# WindPower_HAT_E.net
KiCad netlist of a schematic drawn in EAGLE
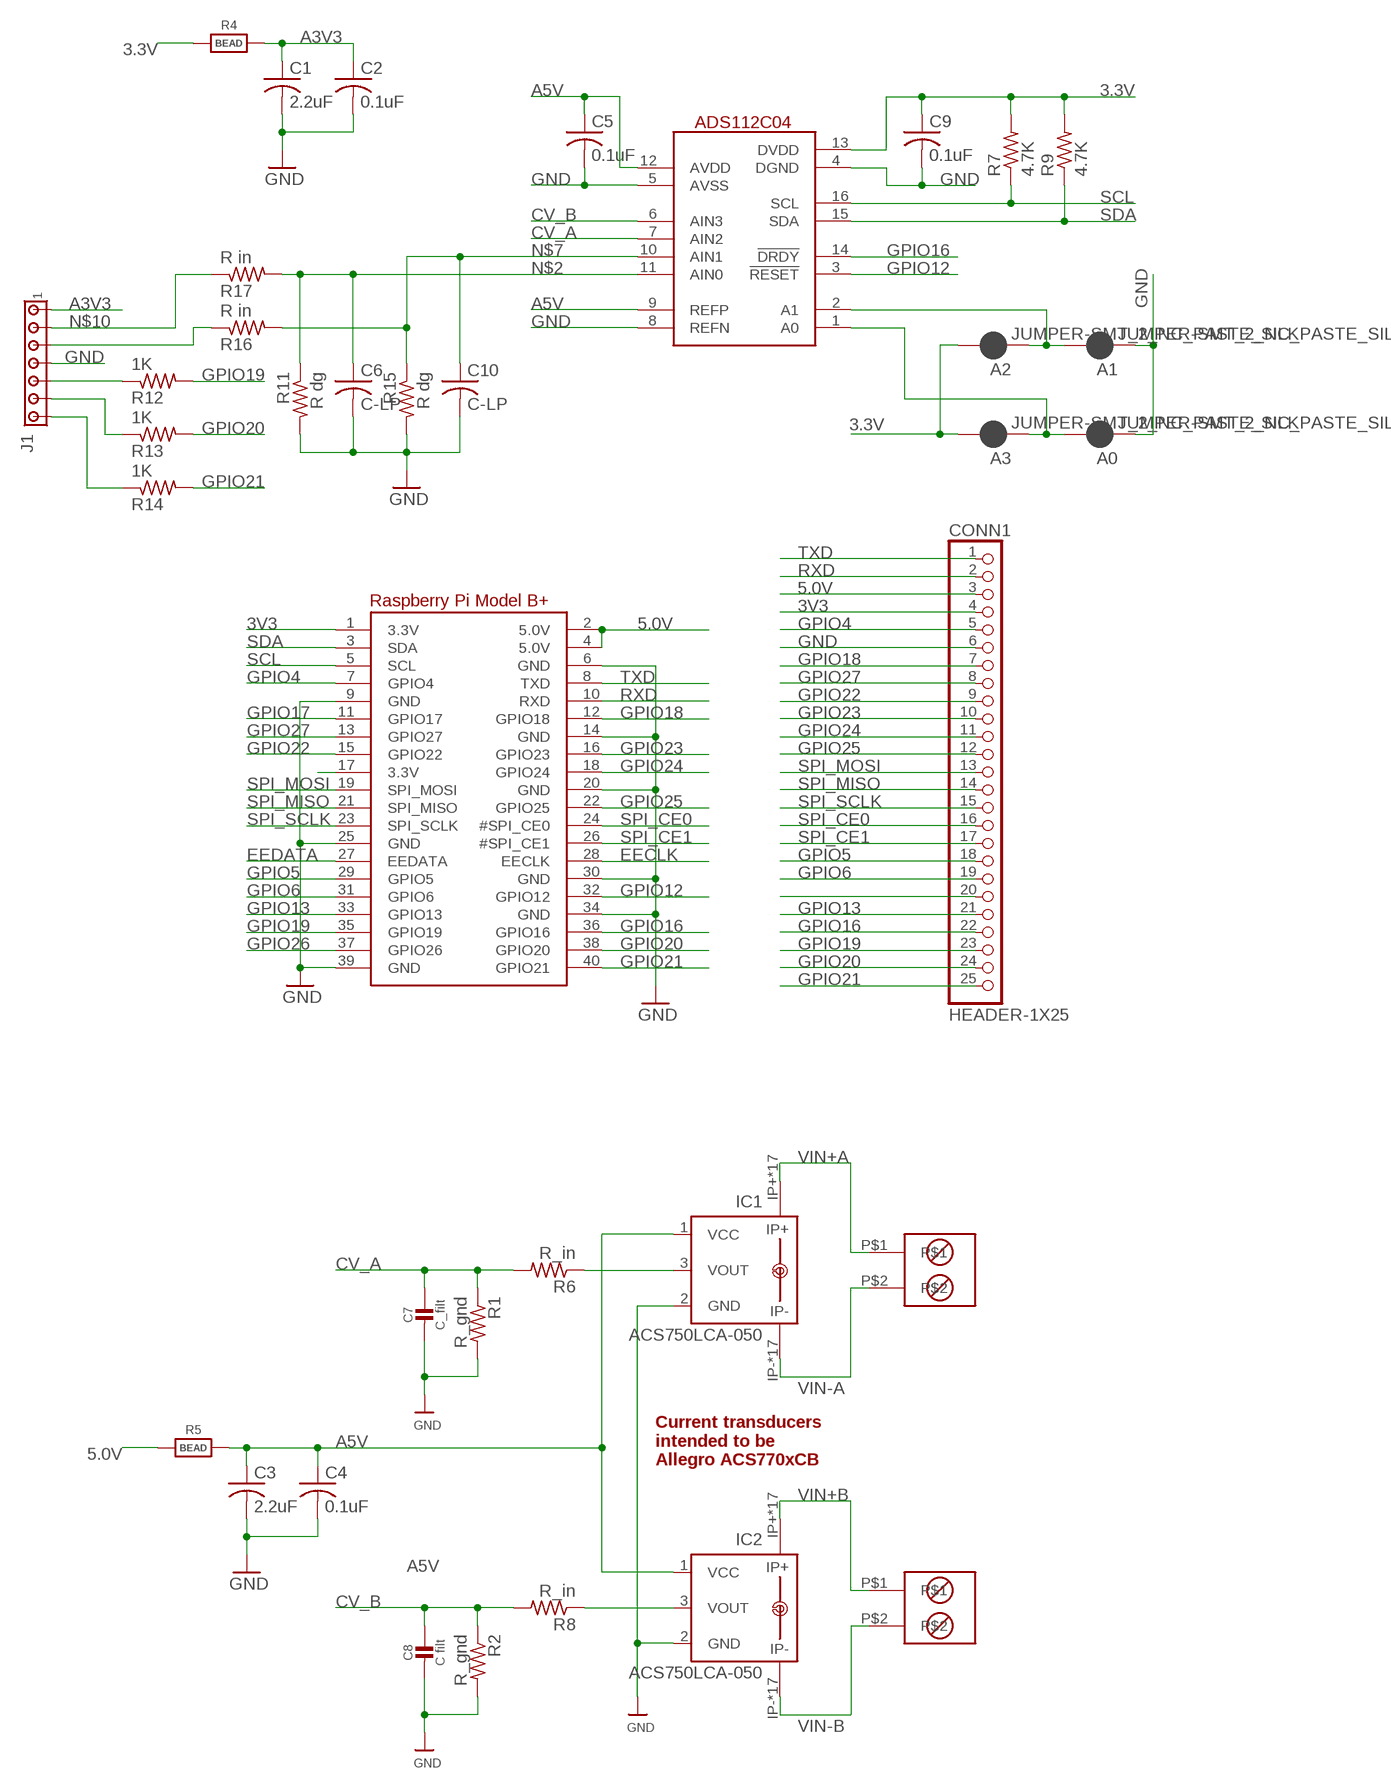
[diagram p0: schematic, sheet 1]

(export (version "E")
  (design (tool "Eeschema 10.0.6"))
  (components
    (comp (ref "A0")
      (value "JUMPER-SMT_2_NC_PASTE_SILK")
      (footprint "eagle-import:SMT-JUMPER_2_NC_PASTE_SILK")
      (libsource (lib "eagle-import") (part "JUMPER-SMT_2_NC_PASTE_SILK"))
    )
    (comp (ref "A1")
      (value "JUMPER-SMT_2_NC_PASTE_SILK")
      (footprint "eagle-import:SMT-JUMPER_2_NC_PASTE_SILK")
      (libsource (lib "eagle-import") (part "JUMPER-SMT_2_NC_PASTE_SILK"))
    )
    (comp (ref "A2")
      (value "JUMPER-SMT_2_NC_PASTE_SILK")
      (footprint "eagle-import:SMT-JUMPER_2_NC_PASTE_SILK")
      (libsource (lib "eagle-import") (part "JUMPER-SMT_2_NC_PASTE_SILK"))
    )
    (comp (ref "A3")
      (value "JUMPER-SMT_2_NC_PASTE_SILK")
      (footprint "eagle-import:SMT-JUMPER_2_NC_PASTE_SILK")
      (libsource (lib "eagle-import") (part "JUMPER-SMT_2_NC_PASTE_SILK"))
    )
    (comp (ref "ADS112C04")
      (value "ADS112C04TSSOP_FOR_TI_ADC")
      (footprint "eagle-import:SOP65P640X120-16N")
      (libsource (lib "eagle-import") (part "ADS112C04TSSOP_FOR_TI_ADC"))
    )
    (comp (ref "C1")
      (value "2.2uF")
      (footprint "eagle-import:C0805")
      (libsource (lib "eagle-import") (part "C-USC0805"))
    )
    (comp (ref "C2")
      (value "0.1uF")
      (footprint "eagle-import:C0805")
      (libsource (lib "eagle-import") (part "C-USC0805"))
    )
    (comp (ref "C3")
      (value "2.2uF")
      (footprint "eagle-import:C0805")
      (libsource (lib "eagle-import") (part "C-USC0805"))
    )
    (comp (ref "C4")
      (value "0.1uF")
      (footprint "eagle-import:C0805")
      (libsource (lib "eagle-import") (part "C-USC0805"))
    )
    (comp (ref "C5")
      (value "0.1uF")
      (footprint "eagle-import:C0805")
      (libsource (lib "eagle-import") (part "C-USC0805"))
    )
    (comp (ref "C6")
      (value "C-LP")
      (footprint "eagle-import:C0805")
      (libsource (lib "eagle-import") (part "C-USC0805"))
    )
    (comp (ref "C7")
      (value "C_filt")
      (footprint "eagle-import:0805-NO@1")
      (libsource (lib "eagle-import") (part "CAP_CERAMIC0805-NOOUTLINE"))
    )
    (comp (ref "C8")
      (value "C filt")
      (footprint "eagle-import:0805-NO@1")
      (libsource (lib "eagle-import") (part "CAP_CERAMIC0805-NOOUTLINE"))
    )
    (comp (ref "C9")
      (value "0.1uF")
      (footprint "eagle-import:C0805")
      (libsource (lib "eagle-import") (part "C-USC0805"))
    )
    (comp (ref "C10")
      (value "C-LP")
      (footprint "eagle-import:C0805")
      (libsource (lib "eagle-import") (part "C-USC0805"))
    )
    (comp (ref "CONN1")
      (value "HEADER-1X25")
      (footprint "eagle-import:1X25_ROUND_70MIL")
      (libsource (lib "eagle-import") (part "HEADER-1X25"))
    )
    (comp (ref "IC1")
      (value "ACS750LCA-050")
      (footprint "eagle-import:ACS75050")
      (fields (field (name "MF") "ALLEGRO MICROSYSTEMS, INC."))
      (libsource (lib "eagle-import") (part "ACS750CA-050L"))
    )
    (comp (ref "IC2")
      (value "ACS750LCA-050")
      (footprint "eagle-import:ACS75050")
      (fields (field (name "MF") "ALLEGRO MICROSYSTEMS, INC."))
      (libsource (lib "eagle-import") (part "ACS750CA-050L"))
    )
    (comp (ref "J1")
      (value "MTA07-100")
      (footprint "eagle-import:10X07MTA")
      (libsource (lib "eagle-import") (part "MTA07-100"))
    )
    (comp (ref "R1")
      (value "R_gnd")
      (footprint "eagle-import:R0805")
      (libsource (lib "eagle-import") (part "R-US_R0805"))
    )
    (comp (ref "R2")
      (value "R_gnd")
      (footprint "eagle-import:R0805")
      (libsource (lib "eagle-import") (part "R-US_R0805"))
    )
    (comp (ref "R4")
      (value "BEAD")
      (footprint "eagle-import:0805-NO")
      (libsource (lib "eagle-import") (part "RESISTOR0805_NOOUTLINE"))
    )
    (comp (ref "R5")
      (value "BEAD")
      (footprint "eagle-import:0805-NO")
      (libsource (lib "eagle-import") (part "RESISTOR0805_NOOUTLINE"))
    )
    (comp (ref "R6")
      (value "R_in")
      (footprint "eagle-import:R0805")
      (libsource (lib "eagle-import") (part "R-US_R0805"))
    )
    (comp (ref "R7")
      (value "4.7K")
      (footprint "eagle-import:R0805")
      (libsource (lib "eagle-import") (part "R-US_R0805"))
    )
    (comp (ref "R8")
      (value "R_in")
      (footprint "eagle-import:R0805")
      (libsource (lib "eagle-import") (part "R-US_R0805"))
    )
    (comp (ref "R9")
      (value "4.7K")
      (footprint "eagle-import:R0805")
      (libsource (lib "eagle-import") (part "R-US_R0805"))
    )
    (comp (ref "R11")
      (value "R dg")
      (footprint "eagle-import:R0805")
      (libsource (lib "eagle-import") (part "R-US_R0805"))
    )
    (comp (ref "R12")
      (value "1K")
      (footprint "eagle-import:R0805")
      (libsource (lib "eagle-import") (part "R-US_R0805"))
    )
    (comp (ref "R13")
      (value "1K")
      (footprint "eagle-import:R0805")
      (libsource (lib "eagle-import") (part "R-US_R0805"))
    )
    (comp (ref "R14")
      (value "1K")
      (footprint "eagle-import:R0805")
      (libsource (lib "eagle-import") (part "R-US_R0805"))
    )
    (comp (ref "R15")
      (value "R dg")
      (footprint "eagle-import:R0805")
      (libsource (lib "eagle-import") (part "R-US_R0805"))
    )
    (comp (ref "R16")
      (value "R in")
      (footprint "eagle-import:R0805")
      (libsource (lib "eagle-import") (part "R-US_R0805"))
    )
    (comp (ref "R17")
      (value "R in")
      (footprint "eagle-import:R0805")
      (libsource (lib "eagle-import") (part "R-US_R0805"))
    )
    (comp (ref "RPI1")
      (value "RASPBERRYPI_BPLUS_HATNOSLOTS")
      (footprint "eagle-import:PI_HAT_NOSLOTS")
      (libsource (lib "eagle-import") (part "RASPBERRYPI_BPLUS_HATNOSLOTS"))
    )
    (comp (ref "U$4")
      (value "SCREW-2-6.35MM")
      (footprint "eagle-import:SCREWY-2-6.35MM")
      (libsource (lib "eagle-import") (part "SCREW-2-6.35MM"))
    )
    (comp (ref "U$5")
      (value "SCREW-2-6.35MM")
      (footprint "eagle-import:SCREWY-2-6.35MM")
      (libsource (lib "eagle-import") (part "SCREW-2-6.35MM"))
    )
  )
  (nets
    (net (code "1") (name "/3V3") (class "Default")
      (node (ref "CONN1") (pin "4") (pinfunction "4_4") (pintype "passive"))
      (node (ref "RPI1") (pin "1") (pinfunction "3.3V_1") (pintype "power_in"))
    )
    (net (code "2") (name "/A3V3") (class "Default")
      (node (ref "C1") (pin "1") (pinfunction "1_1") (pintype "passive"))
      (node (ref "C2") (pin "1") (pinfunction "1_1") (pintype "passive"))
      (node (ref "J1") (pin "1") (pinfunction "1_1") (pintype "passive"))
      (node (ref "R4") (pin "2") (pinfunction "2_2") (pintype "passive"))
    )
    (net (code "3") (name "/A5V") (class "Default")
      (node (ref "ADS112C04") (pin "12") (pinfunction "AVDD_12") (pintype "power_in"))
      (node (ref "ADS112C04") (pin "9") (pinfunction "REFP_9") (pintype "input"))
      (node (ref "C3") (pin "1") (pinfunction "1_1") (pintype "passive"))
      (node (ref "C4") (pin "1") (pinfunction "1_1") (pintype "passive"))
      (node (ref "C5") (pin "1") (pinfunction "1_1") (pintype "passive"))
      (node (ref "IC1") (pin "1") (pinfunction "VCC_1") (pintype "power_in"))
      (node (ref "IC2") (pin "1") (pinfunction "VCC_1") (pintype "power_in"))
      (node (ref "R5") (pin "2") (pinfunction "2_2") (pintype "passive"))
    )
    (net (code "4") (name "/CV_A") (class "Default")
      (node (ref "ADS112C04") (pin "7") (pinfunction "AIN2_7") (pintype "input"))
      (node (ref "C7") (pin "1") (pinfunction "1_1") (pintype "passive"))
      (node (ref "R1") (pin "1") (pinfunction "1_1") (pintype "passive"))
      (node (ref "R6") (pin "2") (pinfunction "2_2") (pintype "passive"))
    )
    (net (code "5") (name "/CV_B") (class "Default")
      (node (ref "ADS112C04") (pin "6") (pinfunction "AIN3_6") (pintype "input"))
      (node (ref "C8") (pin "1") (pinfunction "1_1") (pintype "passive"))
      (node (ref "R2") (pin "1") (pinfunction "1_1") (pintype "passive"))
      (node (ref "R8") (pin "2") (pinfunction "2_2") (pintype "passive"))
    )
    (net (code "6") (name "/EECLK") (class "Default")
      (node (ref "RPI1") (pin "28") (pinfunction "EECLK_28") (pintype "power_in"))
    )
    (net (code "7") (name "/EEDATA") (class "Default")
      (node (ref "RPI1") (pin "27") (pinfunction "EEDATA_27") (pintype "bidirectional"))
    )
    (net (code "8") (name "/GPIO4") (class "Default")
      (node (ref "CONN1") (pin "5") (pinfunction "5_5") (pintype "passive"))
      (node (ref "RPI1") (pin "7") (pinfunction "GPIO4_7") (pintype "bidirectional"))
    )
    (net (code "9") (name "/GPIO5") (class "Default")
      (node (ref "CONN1") (pin "18") (pinfunction "18_18") (pintype "passive"))
      (node (ref "RPI1") (pin "29") (pinfunction "GPIO5_29") (pintype "bidirectional"))
    )
    (net (code "10") (name "/GPIO6") (class "Default")
      (node (ref "CONN1") (pin "19") (pinfunction "19_19") (pintype "passive"))
      (node (ref "RPI1") (pin "31") (pinfunction "GPIO6_31") (pintype "power_in"))
    )
    (net (code "11") (name "/GPIO12") (class "Default")
      (node (ref "ADS112C04") (pin "3") (pinfunction "~{RESET}_3") (pintype "output"))
      (node (ref "RPI1") (pin "32") (pinfunction "GPIO12_32") (pintype "bidirectional"))
    )
    (net (code "12") (name "/GPIO13") (class "Default")
      (node (ref "CONN1") (pin "21") (pinfunction "21_21") (pintype "passive"))
      (node (ref "RPI1") (pin "33") (pinfunction "GPIO13_33") (pintype "bidirectional"))
    )
    (net (code "13") (name "/GPIO16") (class "Default")
      (node (ref "ADS112C04") (pin "14") (pinfunction "~{DRDY}_14") (pintype "output"))
      (node (ref "CONN1") (pin "22") (pinfunction "22_22") (pintype "passive"))
      (node (ref "RPI1") (pin "36") (pinfunction "GPIO16_36") (pintype "power_in"))
    )
    (net (code "14") (name "/GPIO17") (class "Default")
      (node (ref "RPI1") (pin "11") (pinfunction "GPIO17_11") (pintype "bidirectional"))
    )
    (net (code "15") (name "/GPIO18") (class "Default")
      (node (ref "CONN1") (pin "7") (pinfunction "7_7") (pintype "passive"))
      (node (ref "RPI1") (pin "12") (pinfunction "GPIO18_12") (pintype "bidirectional"))
    )
    (net (code "16") (name "/GPIO19") (class "Default")
      (node (ref "CONN1") (pin "23") (pinfunction "23_23") (pintype "passive"))
      (node (ref "R12") (pin "2") (pinfunction "2_2") (pintype "passive"))
      (node (ref "RPI1") (pin "35") (pinfunction "GPIO19_35") (pintype "bidirectional"))
    )
    (net (code "17") (name "/GPIO20") (class "Default")
      (node (ref "CONN1") (pin "24") (pinfunction "24_24") (pintype "passive"))
      (node (ref "R13") (pin "2") (pinfunction "2_2") (pintype "passive"))
      (node (ref "RPI1") (pin "38") (pinfunction "GPIO20_38") (pintype "bidirectional"))
    )
    (net (code "18") (name "/GPIO21") (class "Default")
      (node (ref "CONN1") (pin "25") (pinfunction "25_25") (pintype "passive"))
      (node (ref "R14") (pin "2") (pinfunction "2_2") (pintype "passive"))
      (node (ref "RPI1") (pin "40") (pinfunction "GPIO21_40") (pintype "bidirectional"))
    )
    (net (code "19") (name "/GPIO22") (class "Default")
      (node (ref "CONN1") (pin "9") (pinfunction "9_9") (pintype "passive"))
      (node (ref "RPI1") (pin "15") (pinfunction "GPIO22_15") (pintype "bidirectional"))
    )
    (net (code "20") (name "/GPIO23") (class "Default")
      (node (ref "CONN1") (pin "10") (pinfunction "10_10") (pintype "passive"))
      (node (ref "RPI1") (pin "16") (pinfunction "GPIO23_16") (pintype "bidirectional"))
    )
    (net (code "21") (name "/GPIO24") (class "Default")
      (node (ref "CONN1") (pin "11") (pinfunction "11_11") (pintype "passive"))
      (node (ref "RPI1") (pin "18") (pinfunction "GPIO24_18") (pintype "bidirectional"))
    )
    (net (code "22") (name "/GPIO25") (class "Default")
      (node (ref "CONN1") (pin "12") (pinfunction "12_12") (pintype "passive"))
      (node (ref "RPI1") (pin "22") (pinfunction "GPIO25_22") (pintype "bidirectional"))
    )
    (net (code "23") (name "/GPIO26") (class "Default")
      (node (ref "RPI1") (pin "37") (pinfunction "GPIO26_37") (pintype "bidirectional"))
    )
    (net (code "24") (name "/GPIO27") (class "Default")
      (node (ref "CONN1") (pin "8") (pinfunction "8_8") (pintype "passive"))
      (node (ref "RPI1") (pin "13") (pinfunction "GPIO27_13") (pintype "bidirectional"))
    )
    (net (code "25") (name "/N$2") (class "Default")
      (node (ref "ADS112C04") (pin "11") (pinfunction "AIN0_11") (pintype "input"))
      (node (ref "C6") (pin "1") (pinfunction "1_1") (pintype "passive"))
      (node (ref "R11") (pin "1") (pinfunction "1_1") (pintype "passive"))
      (node (ref "R17") (pin "2") (pinfunction "2_2") (pintype "passive"))
    )
    (net (code "26") (name "/N$7") (class "Default")
      (node (ref "ADS112C04") (pin "10") (pinfunction "AIN1_10") (pintype "input"))
      (node (ref "C10") (pin "1") (pinfunction "1_1") (pintype "passive"))
      (node (ref "R15") (pin "1") (pinfunction "1_1") (pintype "passive"))
      (node (ref "R16") (pin "2") (pinfunction "2_2") (pintype "passive"))
    )
    (net (code "27") (name "/N$10") (class "Default")
      (node (ref "J1") (pin "2") (pinfunction "2_2") (pintype "passive"))
      (node (ref "R17") (pin "1") (pinfunction "1_1") (pintype "passive"))
    )
    (net (code "28") (name "/RXD") (class "Default")
      (node (ref "CONN1") (pin "2") (pinfunction "2_2") (pintype "passive"))
      (node (ref "RPI1") (pin "10") (pinfunction "RXD_10") (pintype "bidirectional"))
    )
    (net (code "29") (name "/SCL") (class "Default")
      (node (ref "ADS112C04") (pin "16") (pinfunction "SCL_16") (pintype "input"))
      (node (ref "R7") (pin "1") (pinfunction "1_1") (pintype "passive"))
      (node (ref "RPI1") (pin "5") (pinfunction "SCL_5") (pintype "bidirectional"))
    )
    (net (code "30") (name "/SDA") (class "Default")
      (node (ref "ADS112C04") (pin "15") (pinfunction "SDA_15") (pintype "bidirectional"))
      (node (ref "R9") (pin "1") (pinfunction "1_1") (pintype "passive"))
      (node (ref "RPI1") (pin "3") (pinfunction "SDA_3") (pintype "bidirectional"))
    )
    (net (code "31") (name "/SPI_CE0") (class "Default")
      (node (ref "CONN1") (pin "16") (pinfunction "16_16") (pintype "passive"))
      (node (ref "RPI1") (pin "24") (pinfunction "#SPI_CE0_24") (pintype "bidirectional"))
    )
    (net (code "32") (name "/SPI_CE1") (class "Default")
      (node (ref "CONN1") (pin "17") (pinfunction "17_17") (pintype "passive"))
      (node (ref "RPI1") (pin "26") (pinfunction "#SPI_CE1_26") (pintype "bidirectional"))
    )
    (net (code "33") (name "/SPI_MISO") (class "Default")
      (node (ref "CONN1") (pin "14") (pinfunction "14_14") (pintype "passive"))
      (node (ref "RPI1") (pin "21") (pinfunction "SPI_MISO_21") (pintype "bidirectional"))
    )
    (net (code "34") (name "/SPI_MOSI") (class "Default")
      (node (ref "CONN1") (pin "13") (pinfunction "13_13") (pintype "passive"))
      (node (ref "RPI1") (pin "19") (pinfunction "SPI_MOSI_19") (pintype "bidirectional"))
    )
    (net (code "35") (name "/SPI_SCLK") (class "Default")
      (node (ref "CONN1") (pin "15") (pinfunction "15_15") (pintype "passive"))
      (node (ref "RPI1") (pin "23") (pinfunction "SPI_SCLK_23") (pintype "bidirectional"))
    )
    (net (code "36") (name "/TXD") (class "Default")
      (node (ref "CONN1") (pin "1") (pinfunction "1_1") (pintype "passive"))
      (node (ref "RPI1") (pin "8") (pinfunction "TXD_8") (pintype "output"))
    )
    (net (code "37") (name "/VIN+A") (class "Default")
      (node (ref "IC1") (pin "IP+") (pinfunction "IP+_IP+") (pintype "passive"))
      (node (ref "IC1") (pin "IP+@10") (pinfunction "IP+_IP+@10") (pintype "passive"))
      (node (ref "IC1") (pin "IP+@11") (pinfunction "IP+_IP+@11") (pintype "passive"))
      (node (ref "IC1") (pin "IP+@12") (pinfunction "IP+_IP+@12") (pintype "passive"))
      (node (ref "IC1") (pin "IP+@13") (pinfunction "IP+_IP+@13") (pintype "passive"))
      (node (ref "IC1") (pin "IP+@14") (pinfunction "IP+_IP+@14") (pintype "passive"))
      (node (ref "IC1") (pin "IP+@15") (pinfunction "IP+_IP+@15") (pintype "passive"))
      (node (ref "IC1") (pin "IP+@16") (pinfunction "IP+_IP+@16") (pintype "passive"))
      (node (ref "IC1") (pin "IP+@17") (pinfunction "IP+_IP+@17") (pintype "passive"))
      (node (ref "IC1") (pin "IP+@2") (pinfunction "IP+_IP+@2") (pintype "passive"))
      (node (ref "IC1") (pin "IP+@3") (pinfunction "IP+_IP+@3") (pintype "passive"))
      (node (ref "IC1") (pin "IP+@4") (pinfunction "IP+_IP+@4") (pintype "passive"))
      (node (ref "IC1") (pin "IP+@5") (pinfunction "IP+_IP+@5") (pintype "passive"))
      (node (ref "IC1") (pin "IP+@6") (pinfunction "IP+_IP+@6") (pintype "passive"))
      (node (ref "IC1") (pin "IP+@7") (pinfunction "IP+_IP+@7") (pintype "passive"))
      (node (ref "IC1") (pin "IP+@8") (pinfunction "IP+_IP+@8") (pintype "passive"))
      (node (ref "IC1") (pin "IP+@9") (pinfunction "IP+_IP+@9") (pintype "passive"))
      (node (ref "U$4") (pin "P$1") (pinfunction "P$1_P$1") (pintype "bidirectional"))
    )
    (net (code "38") (name "/VIN+B") (class "Default")
      (node (ref "IC2") (pin "IP+") (pinfunction "IP+_IP+") (pintype "passive"))
      (node (ref "IC2") (pin "IP+@10") (pinfunction "IP+_IP+@10") (pintype "passive"))
      (node (ref "IC2") (pin "IP+@11") (pinfunction "IP+_IP+@11") (pintype "passive"))
      (node (ref "IC2") (pin "IP+@12") (pinfunction "IP+_IP+@12") (pintype "passive"))
      (node (ref "IC2") (pin "IP+@13") (pinfunction "IP+_IP+@13") (pintype "passive"))
      (node (ref "IC2") (pin "IP+@14") (pinfunction "IP+_IP+@14") (pintype "passive"))
      (node (ref "IC2") (pin "IP+@15") (pinfunction "IP+_IP+@15") (pintype "passive"))
      (node (ref "IC2") (pin "IP+@16") (pinfunction "IP+_IP+@16") (pintype "passive"))
      (node (ref "IC2") (pin "IP+@17") (pinfunction "IP+_IP+@17") (pintype "passive"))
      (node (ref "IC2") (pin "IP+@2") (pinfunction "IP+_IP+@2") (pintype "passive"))
      (node (ref "IC2") (pin "IP+@3") (pinfunction "IP+_IP+@3") (pintype "passive"))
      (node (ref "IC2") (pin "IP+@4") (pinfunction "IP+_IP+@4") (pintype "passive"))
      (node (ref "IC2") (pin "IP+@5") (pinfunction "IP+_IP+@5") (pintype "passive"))
      (node (ref "IC2") (pin "IP+@6") (pinfunction "IP+_IP+@6") (pintype "passive"))
      (node (ref "IC2") (pin "IP+@7") (pinfunction "IP+_IP+@7") (pintype "passive"))
      (node (ref "IC2") (pin "IP+@8") (pinfunction "IP+_IP+@8") (pintype "passive"))
      (node (ref "IC2") (pin "IP+@9") (pinfunction "IP+_IP+@9") (pintype "passive"))
      (node (ref "U$5") (pin "P$1") (pinfunction "P$1_P$1") (pintype "bidirectional"))
    )
    (net (code "39") (name "/VIN-A") (class "Default")
      (node (ref "IC1") (pin "IP-") (pinfunction "IP-_IP-") (pintype "passive"))
      (node (ref "IC1") (pin "IP-@10") (pinfunction "IP-_IP-@10") (pintype "passive"))
      (node (ref "IC1") (pin "IP-@11") (pinfunction "IP-_IP-@11") (pintype "passive"))
      (node (ref "IC1") (pin "IP-@12") (pinfunction "IP-_IP-@12") (pintype "passive"))
      (node (ref "IC1") (pin "IP-@13") (pinfunction "IP-_IP-@13") (pintype "passive"))
      (node (ref "IC1") (pin "IP-@14") (pinfunction "IP-_IP-@14") (pintype "passive"))
      (node (ref "IC1") (pin "IP-@15") (pinfunction "IP-_IP-@15") (pintype "passive"))
      (node (ref "IC1") (pin "IP-@16") (pinfunction "IP-_IP-@16") (pintype "passive"))
      (node (ref "IC1") (pin "IP-@17") (pinfunction "IP-_IP-@17") (pintype "passive"))
      (node (ref "IC1") (pin "IP-@2") (pinfunction "IP-_IP-@2") (pintype "passive"))
      (node (ref "IC1") (pin "IP-@3") (pinfunction "IP-_IP-@3") (pintype "passive"))
      (node (ref "IC1") (pin "IP-@4") (pinfunction "IP-_IP-@4") (pintype "passive"))
      (node (ref "IC1") (pin "IP-@5") (pinfunction "IP-_IP-@5") (pintype "passive"))
      (node (ref "IC1") (pin "IP-@6") (pinfunction "IP-_IP-@6") (pintype "passive"))
      (node (ref "IC1") (pin "IP-@7") (pinfunction "IP-_IP-@7") (pintype "passive"))
      (node (ref "IC1") (pin "IP-@8") (pinfunction "IP-_IP-@8") (pintype "passive"))
      (node (ref "IC1") (pin "IP-@9") (pinfunction "IP-_IP-@9") (pintype "passive"))
      (node (ref "U$4") (pin "P$2") (pinfunction "P$2_P$2") (pintype "bidirectional"))
    )
    (net (code "40") (name "/VIN-B") (class "Default")
      (node (ref "IC2") (pin "IP-") (pinfunction "IP-_IP-") (pintype "passive"))
      (node (ref "IC2") (pin "IP-@10") (pinfunction "IP-_IP-@10") (pintype "passive"))
      (node (ref "IC2") (pin "IP-@11") (pinfunction "IP-_IP-@11") (pintype "passive"))
      (node (ref "IC2") (pin "IP-@12") (pinfunction "IP-_IP-@12") (pintype "passive"))
      (node (ref "IC2") (pin "IP-@13") (pinfunction "IP-_IP-@13") (pintype "passive"))
      (node (ref "IC2") (pin "IP-@14") (pinfunction "IP-_IP-@14") (pintype "passive"))
      (node (ref "IC2") (pin "IP-@15") (pinfunction "IP-_IP-@15") (pintype "passive"))
      (node (ref "IC2") (pin "IP-@16") (pinfunction "IP-_IP-@16") (pintype "passive"))
      (node (ref "IC2") (pin "IP-@17") (pinfunction "IP-_IP-@17") (pintype "passive"))
      (node (ref "IC2") (pin "IP-@2") (pinfunction "IP-_IP-@2") (pintype "passive"))
      (node (ref "IC2") (pin "IP-@3") (pinfunction "IP-_IP-@3") (pintype "passive"))
      (node (ref "IC2") (pin "IP-@4") (pinfunction "IP-_IP-@4") (pintype "passive"))
      (node (ref "IC2") (pin "IP-@5") (pinfunction "IP-_IP-@5") (pintype "passive"))
      (node (ref "IC2") (pin "IP-@6") (pinfunction "IP-_IP-@6") (pintype "passive"))
      (node (ref "IC2") (pin "IP-@7") (pinfunction "IP-_IP-@7") (pintype "passive"))
      (node (ref "IC2") (pin "IP-@8") (pinfunction "IP-_IP-@8") (pintype "passive"))
      (node (ref "IC2") (pin "IP-@9") (pinfunction "IP-_IP-@9") (pintype "passive"))
      (node (ref "U$5") (pin "P$2") (pinfunction "P$2_P$2") (pintype "bidirectional"))
    )
    (net (code "41") (name "3.3V") (class "Default")
      (node (ref "A2") (pin "2") (pinfunction "2_2") (pintype "passive"))
      (node (ref "A3") (pin "2") (pinfunction "2_2") (pintype "passive"))
      (node (ref "ADS112C04") (pin "13") (pinfunction "DVDD_13") (pintype "power_in"))
      (node (ref "C9") (pin "1") (pinfunction "1_1") (pintype "passive"))
      (node (ref "R4") (pin "1") (pinfunction "1_1") (pintype "passive"))
      (node (ref "R7") (pin "2") (pinfunction "2_2") (pintype "passive"))
      (node (ref "R9") (pin "2") (pinfunction "2_2") (pintype "passive"))
      (node (ref "RPI1") (pin "17") (pinfunction "3.3V_17") (pintype "power_in"))
    )
    (net (code "42") (name "5.0V") (class "Default")
      (node (ref "CONN1") (pin "3") (pinfunction "3_3") (pintype "passive"))
      (node (ref "R5") (pin "1") (pinfunction "1_1") (pintype "passive"))
      (node (ref "RPI1") (pin "2") (pinfunction "5.0V_2") (pintype "power_in"))
      (node (ref "RPI1") (pin "4") (pinfunction "5.0V_4") (pintype "power_in"))
    )
    (net (code "43") (name "GND") (class "Default")
      (node (ref "A0") (pin "1") (pinfunction "1_1") (pintype "passive"))
      (node (ref "A1") (pin "1") (pinfunction "1_1") (pintype "passive"))
      (node (ref "ADS112C04") (pin "4") (pinfunction "DGND_4") (pintype "power_in"))
      (node (ref "ADS112C04") (pin "5") (pinfunction "AVSS_5") (pintype "power_in"))
      (node (ref "ADS112C04") (pin "8") (pinfunction "REFN_8") (pintype "input"))
      (node (ref "C1") (pin "2") (pinfunction "2_2") (pintype "passive"))
      (node (ref "C10") (pin "2") (pinfunction "2_2") (pintype "passive"))
      (node (ref "C2") (pin "2") (pinfunction "2_2") (pintype "passive"))
      (node (ref "C3") (pin "2") (pinfunction "2_2") (pintype "passive"))
      (node (ref "C4") (pin "2") (pinfunction "2_2") (pintype "passive"))
      (node (ref "C5") (pin "2") (pinfunction "2_2") (pintype "passive"))
      (node (ref "C6") (pin "2") (pinfunction "2_2") (pintype "passive"))
      (node (ref "C7") (pin "2") (pinfunction "2_2") (pintype "passive"))
      (node (ref "C8") (pin "2") (pinfunction "2_2") (pintype "passive"))
      (node (ref "C9") (pin "2") (pinfunction "2_2") (pintype "passive"))
      (node (ref "CONN1") (pin "20") (pinfunction "20_20") (pintype "passive"))
      (node (ref "CONN1") (pin "6") (pinfunction "6_6") (pintype "passive"))
      (node (ref "IC1") (pin "2") (pinfunction "GND_2") (pintype "power_in"))
      (node (ref "IC2") (pin "2") (pinfunction "GND_2") (pintype "power_in"))
      (node (ref "J1") (pin "4") (pinfunction "4_4") (pintype "passive"))
      (node (ref "R1") (pin "2") (pinfunction "2_2") (pintype "passive"))
      (node (ref "R11") (pin "2") (pinfunction "2_2") (pintype "passive"))
      (node (ref "R15") (pin "2") (pinfunction "2_2") (pintype "passive"))
      (node (ref "R2") (pin "2") (pinfunction "2_2") (pintype "passive"))
      (node (ref "RPI1") (pin "14") (pinfunction "GND_14") (pintype "power_in"))
      (node (ref "RPI1") (pin "20") (pinfunction "GND_20") (pintype "power_in"))
      (node (ref "RPI1") (pin "25") (pinfunction "GND_25") (pintype "power_in"))
      (node (ref "RPI1") (pin "30") (pinfunction "GND_30") (pintype "bidirectional"))
      (node (ref "RPI1") (pin "34") (pinfunction "GND_34") (pintype "bidirectional"))
      (node (ref "RPI1") (pin "39") (pinfunction "GND_39") (pintype "power_in"))
      (node (ref "RPI1") (pin "6") (pinfunction "GND_6") (pintype "power_in"))
      (node (ref "RPI1") (pin "9") (pinfunction "GND_9") (pintype "power_in"))
    )
    (net (code "44") (name "Net-(ADS112C04-A0)") (class "Default")
      (node (ref "A0") (pin "2") (pinfunction "2_2") (pintype "passive"))
      (node (ref "A3") (pin "1") (pinfunction "1_1") (pintype "passive"))
      (node (ref "ADS112C04") (pin "1") (pinfunction "A0_1") (pintype "bidirectional"))
    )
    (net (code "45") (name "Net-(ADS112C04-A1)") (class "Default")
      (node (ref "A1") (pin "2") (pinfunction "2_2") (pintype "passive"))
      (node (ref "A2") (pin "1") (pinfunction "1_1") (pintype "passive"))
      (node (ref "ADS112C04") (pin "2") (pinfunction "A1_2") (pintype "bidirectional"))
    )
    (net (code "46") (name "Net-(IC1-VOUT)") (class "Default")
      (node (ref "IC1") (pin "3") (pinfunction "VOUT_3") (pintype "output"))
      (node (ref "R6") (pin "1") (pinfunction "1_1") (pintype "passive"))
    )
    (net (code "47") (name "Net-(IC2-VOUT)") (class "Default")
      (node (ref "IC2") (pin "3") (pinfunction "VOUT_3") (pintype "output"))
      (node (ref "R8") (pin "1") (pinfunction "1_1") (pintype "passive"))
    )
    (net (code "48") (name "Net-(J1-Pad3)") (class "Default")
      (node (ref "J1") (pin "3") (pinfunction "3_3") (pintype "passive"))
      (node (ref "R16") (pin "1") (pinfunction "1_1") (pintype "passive"))
    )
    (net (code "49") (name "Net-(J1-Pad5)") (class "Default")
      (node (ref "J1") (pin "5") (pinfunction "5_5") (pintype "passive"))
      (node (ref "R12") (pin "1") (pinfunction "1_1") (pintype "passive"))
    )
    (net (code "50") (name "Net-(J1-Pad6)") (class "Default")
      (node (ref "J1") (pin "6") (pinfunction "6_6") (pintype "passive"))
      (node (ref "R13") (pin "1") (pinfunction "1_1") (pintype "passive"))
    )
    (net (code "51") (name "Net-(J1-Pad7)") (class "Default")
      (node (ref "J1") (pin "7") (pinfunction "7_7") (pintype "passive"))
      (node (ref "R14") (pin "1") (pinfunction "1_1") (pintype "passive"))
    )
  )
)
